# psuboardBetter.net
KiCad netlist of a schematic drawn in EAGLE
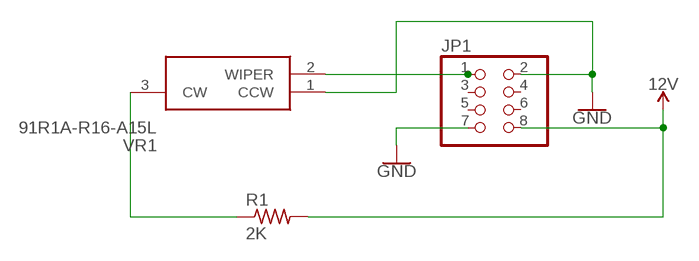
[diagram p0: schematic, sheet 1]

(export (version "E")
  (design (tool "Eeschema 10.0.6"))
  (components
    (comp (ref "JP1")
      (value "PINHD-2X4")
      (footprint "eagle-import:2X04")
      (libsource (lib "eagle-import") (part "PINHD-2X4"))
    )
    (comp (ref "R1")
      (value "2K")
      (footprint "eagle-import:R0805")
      (libsource (lib "eagle-import") (part "R-US_R0805"))
    )
    (comp (ref "VR1")
      (value "91R1A-R16-A15L")
      (footprint "eagle-import:91R1AR16A15L")
      (fields (field (name "MOUSER_PART_NUMBER") "652-91R1A-R16-A15L"))
      (libsource (lib "eagle-import") (part "91R1A-R16-A15L"))
    )
  )
  (nets
    (net (code "1") (name "12V") (class "Default")
      (node (ref "JP1") (pin "8") (pinfunction "8_8") (pintype "passive"))
      (node (ref "R1") (pin "2") (pinfunction "2_2") (pintype "passive"))
    )
    (net (code "2") (name "GND") (class "Default")
      (node (ref "JP1") (pin "2") (pinfunction "2_2") (pintype "passive"))
      (node (ref "JP1") (pin "7") (pinfunction "7_7") (pintype "passive"))
      (node (ref "VR1") (pin "1") (pinfunction "CCW_1") (pintype "bidirectional"))
    )
    (net (code "3") (name "Net-(VR1-CW)") (class "Default")
      (node (ref "R1") (pin "1") (pinfunction "1_1") (pintype "passive"))
      (node (ref "VR1") (pin "3") (pinfunction "CW_3") (pintype "bidirectional"))
    )
    (net (code "4") (name "Net-(VR1-WIPER)") (class "Default")
      (node (ref "JP1") (pin "1") (pinfunction "1_1") (pintype "passive"))
      (node (ref "VR1") (pin "2") (pinfunction "WIPER_2") (pintype "bidirectional"))
    )
    (net (code "5") (name "unconnected-(JP1-Pad3)") (class "Default")
      (node (ref "JP1") (pin "3") (pinfunction "3_3") (pintype "passive"))
    )
    (net (code "6") (name "unconnected-(JP1-Pad4)") (class "Default")
      (node (ref "JP1") (pin "4") (pinfunction "4_4") (pintype "passive"))
    )
    (net (code "7") (name "unconnected-(JP1-Pad5)") (class "Default")
      (node (ref "JP1") (pin "5") (pinfunction "5_5") (pintype "passive"))
    )
    (net (code "8") (name "unconnected-(JP1-Pad6)") (class "Default")
      (node (ref "JP1") (pin "6") (pinfunction "6_6") (pintype "passive"))
    )
  )
)
